# design.net
KiCad netlist of a schematic drawn in Altium Designer
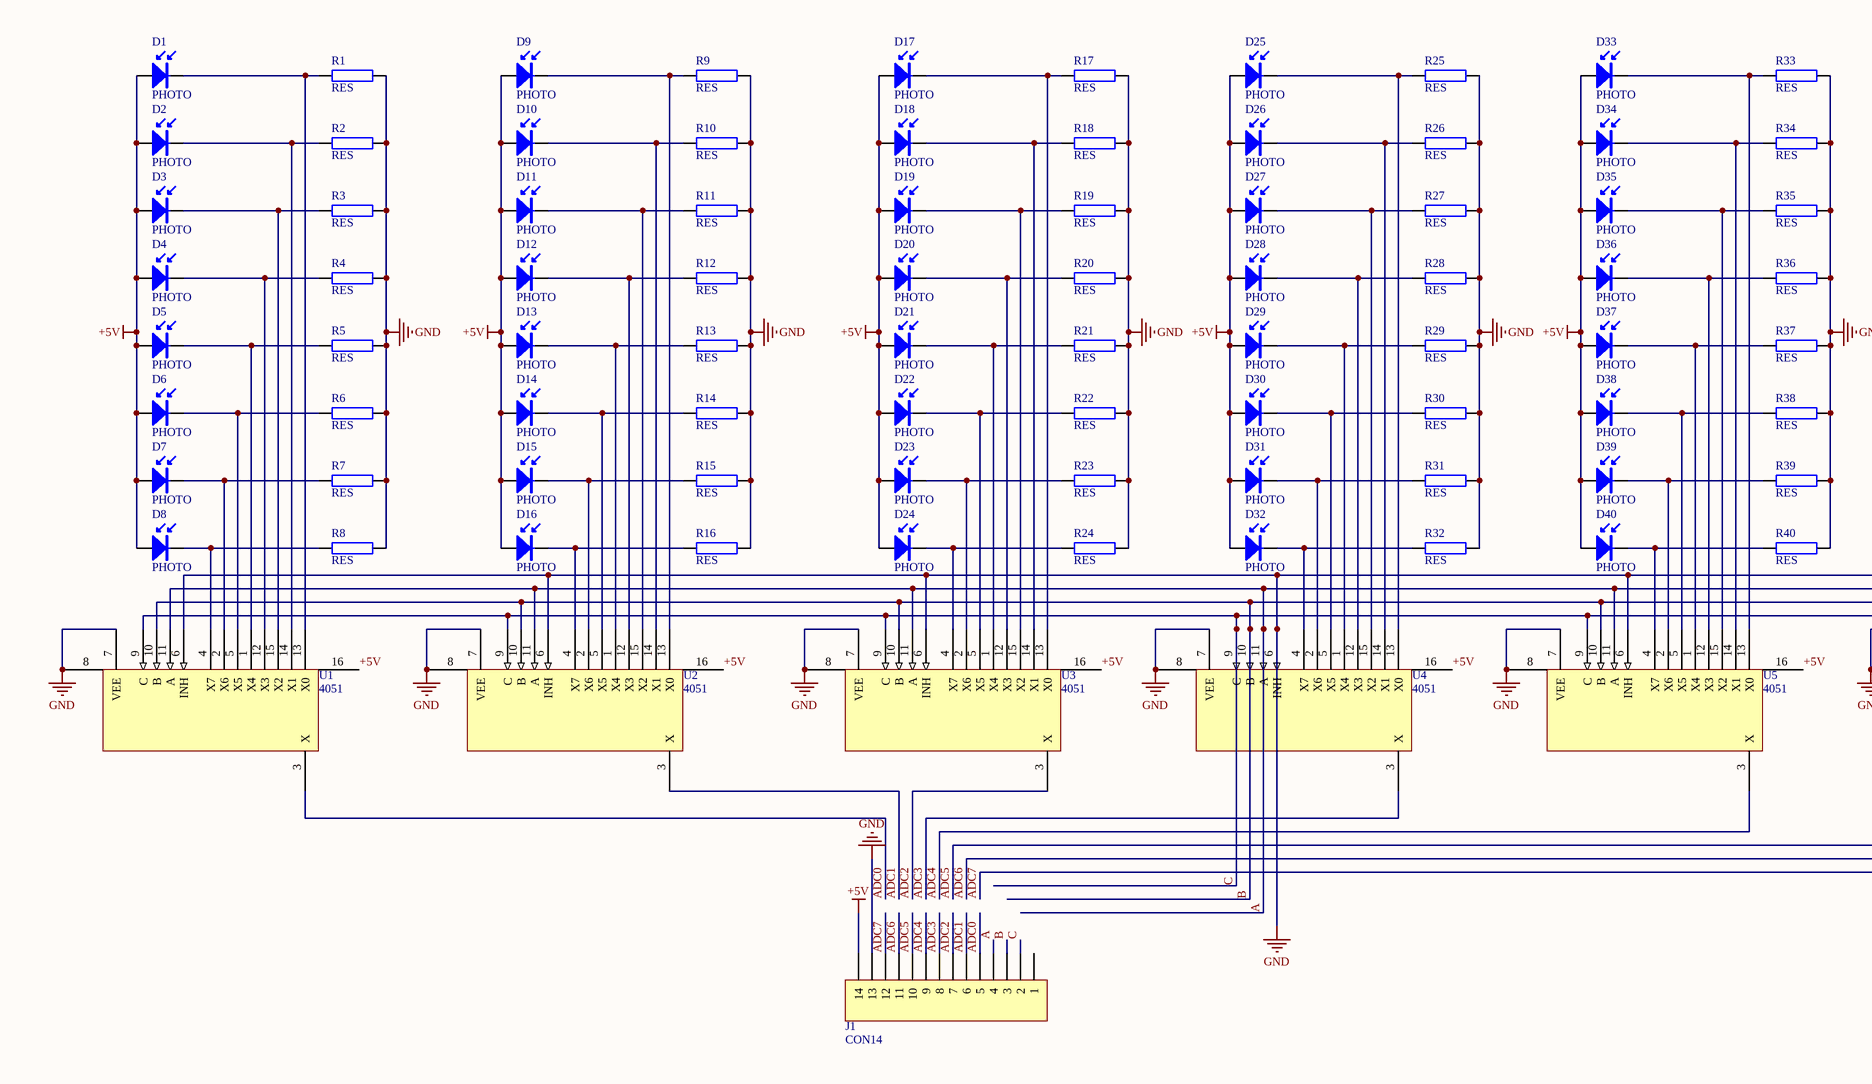
[diagram p0: 光阵列版.SchDoc, left]
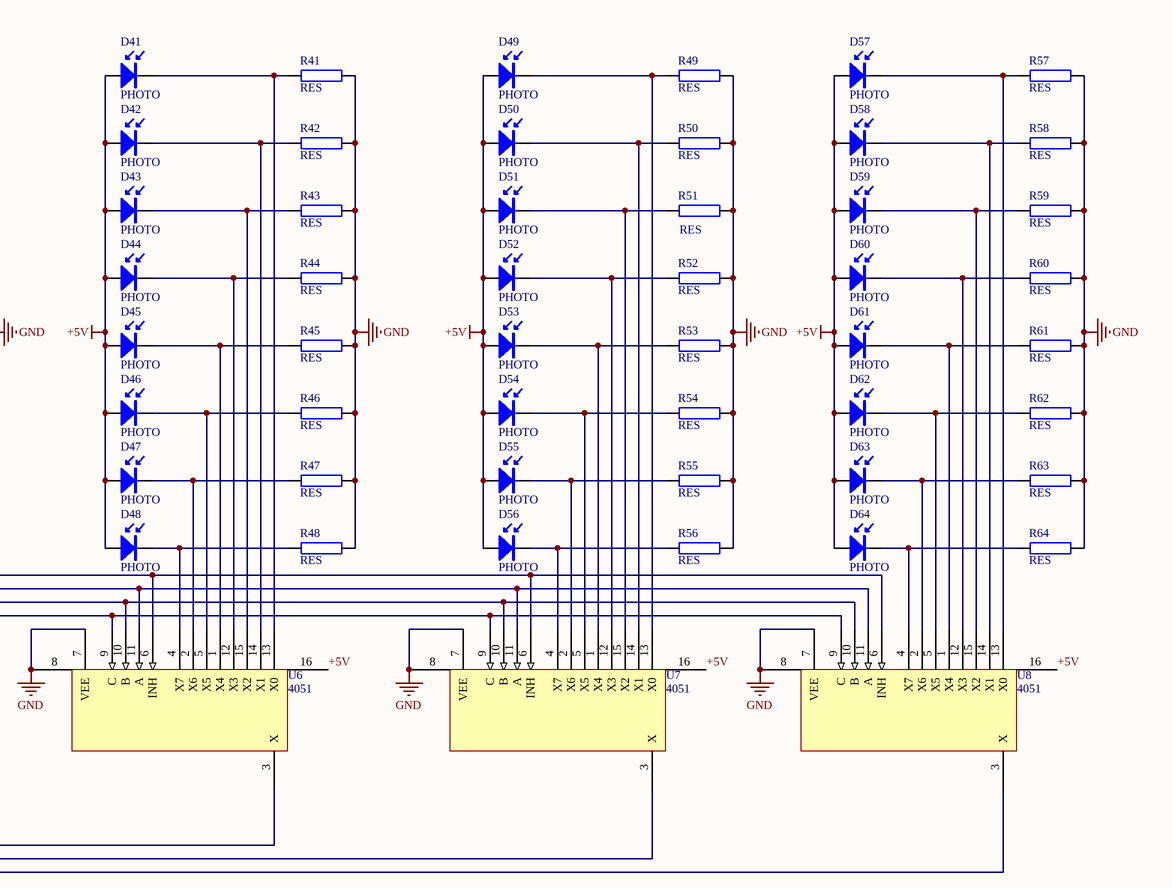
[diagram p1: 光阵列版.SchDoc, right]

(export (version "E")
  (design (tool "Eeschema 10.0.6"))
  (components
    (comp (ref "D1")
      (value "PHOTO")
      (footprint "LED2")
      (description "Photosensitive Diode")
      (libsource (lib "Diode二极管") (part "PHOTO"))
    )
    (comp (ref "D2")
      (value "PHOTO")
      (footprint "LED2")
      (description "Photosensitive Diode")
      (libsource (lib "Diode二极管") (part "PHOTO"))
    )
    (comp (ref "D3")
      (value "PHOTO")
      (footprint "LED2")
      (description "Photosensitive Diode")
      (libsource (lib "Diode二极管") (part "PHOTO"))
    )
    (comp (ref "D4")
      (value "PHOTO")
      (footprint "LED2")
      (description "Photosensitive Diode")
      (libsource (lib "Diode二极管") (part "PHOTO"))
    )
    (comp (ref "D5")
      (value "PHOTO")
      (footprint "LED2")
      (description "Photosensitive Diode")
      (libsource (lib "Diode二极管") (part "PHOTO"))
    )
    (comp (ref "D6")
      (value "PHOTO")
      (footprint "LED2")
      (description "Photosensitive Diode")
      (libsource (lib "Diode二极管") (part "PHOTO"))
    )
    (comp (ref "D7")
      (value "PHOTO")
      (footprint "LED2")
      (description "Photosensitive Diode")
      (libsource (lib "Diode二极管") (part "PHOTO"))
    )
    (comp (ref "D8")
      (value "PHOTO")
      (footprint "LED2")
      (description "Photosensitive Diode")
      (libsource (lib "Diode二极管") (part "PHOTO"))
    )
    (comp (ref "D9")
      (value "PHOTO")
      (footprint "LED2")
      (description "Photosensitive Diode")
      (libsource (lib "Diode二极管") (part "PHOTO"))
    )
    (comp (ref "D10")
      (value "PHOTO")
      (footprint "LED2")
      (description "Photosensitive Diode")
      (libsource (lib "Diode二极管") (part "PHOTO"))
    )
    (comp (ref "D11")
      (value "PHOTO")
      (footprint "LED2")
      (description "Photosensitive Diode")
      (libsource (lib "Diode二极管") (part "PHOTO"))
    )
    (comp (ref "D12")
      (value "PHOTO")
      (footprint "LED2")
      (description "Photosensitive Diode")
      (libsource (lib "Diode二极管") (part "PHOTO"))
    )
    (comp (ref "D13")
      (value "PHOTO")
      (footprint "LED2")
      (description "Photosensitive Diode")
      (libsource (lib "Diode二极管") (part "PHOTO"))
    )
    (comp (ref "D14")
      (value "PHOTO")
      (footprint "LED2")
      (description "Photosensitive Diode")
      (libsource (lib "Diode二极管") (part "PHOTO"))
    )
    (comp (ref "D15")
      (value "PHOTO")
      (footprint "LED2")
      (description "Photosensitive Diode")
      (libsource (lib "Diode二极管") (part "PHOTO"))
    )
    (comp (ref "D16")
      (value "PHOTO")
      (footprint "LED2")
      (description "Photosensitive Diode")
      (libsource (lib "Diode二极管") (part "PHOTO"))
    )
    (comp (ref "D17")
      (value "PHOTO")
      (footprint "LED2")
      (description "Photosensitive Diode")
      (libsource (lib "Diode二极管") (part "PHOTO"))
    )
    (comp (ref "D18")
      (value "PHOTO")
      (footprint "LED2")
      (description "Photosensitive Diode")
      (libsource (lib "Diode二极管") (part "PHOTO"))
    )
    (comp (ref "D19")
      (value "PHOTO")
      (footprint "LED2")
      (description "Photosensitive Diode")
      (libsource (lib "Diode二极管") (part "PHOTO"))
    )
    (comp (ref "D20")
      (value "PHOTO")
      (footprint "LED2")
      (description "Photosensitive Diode")
      (libsource (lib "Diode二极管") (part "PHOTO"))
    )
    (comp (ref "D21")
      (value "PHOTO")
      (footprint "LED2")
      (description "Photosensitive Diode")
      (libsource (lib "Diode二极管") (part "PHOTO"))
    )
    (comp (ref "D22")
      (value "PHOTO")
      (footprint "LED2")
      (description "Photosensitive Diode")
      (libsource (lib "Diode二极管") (part "PHOTO"))
    )
    (comp (ref "D23")
      (value "PHOTO")
      (footprint "LED2")
      (description "Photosensitive Diode")
      (libsource (lib "Diode二极管") (part "PHOTO"))
    )
    (comp (ref "D24")
      (value "PHOTO")
      (footprint "LED2")
      (description "Photosensitive Diode")
      (libsource (lib "Diode二极管") (part "PHOTO"))
    )
    (comp (ref "D25")
      (value "PHOTO")
      (footprint "LED2")
      (description "Photosensitive Diode")
      (libsource (lib "Diode二极管") (part "PHOTO"))
    )
    (comp (ref "D26")
      (value "PHOTO")
      (footprint "LED2")
      (description "Photosensitive Diode")
      (libsource (lib "Diode二极管") (part "PHOTO"))
    )
    (comp (ref "D27")
      (value "PHOTO")
      (footprint "LED2")
      (description "Photosensitive Diode")
      (libsource (lib "Diode二极管") (part "PHOTO"))
    )
    (comp (ref "D28")
      (value "PHOTO")
      (footprint "LED2")
      (description "Photosensitive Diode")
      (libsource (lib "Diode二极管") (part "PHOTO"))
    )
    (comp (ref "D29")
      (value "PHOTO")
      (footprint "LED2")
      (description "Photosensitive Diode")
      (libsource (lib "Diode二极管") (part "PHOTO"))
    )
    (comp (ref "D30")
      (value "PHOTO")
      (footprint "LED2")
      (description "Photosensitive Diode")
      (libsource (lib "Diode二极管") (part "PHOTO"))
    )
    (comp (ref "D31")
      (value "PHOTO")
      (footprint "LED2")
      (description "Photosensitive Diode")
      (libsource (lib "Diode二极管") (part "PHOTO"))
    )
    (comp (ref "D32")
      (value "PHOTO")
      (footprint "LED2")
      (description "Photosensitive Diode")
      (libsource (lib "Diode二极管") (part "PHOTO"))
    )
    (comp (ref "D33")
      (value "PHOTO")
      (footprint "LED2")
      (description "Photosensitive Diode")
      (libsource (lib "Diode二极管") (part "PHOTO"))
    )
    (comp (ref "D34")
      (value "PHOTO")
      (footprint "LED2")
      (description "Photosensitive Diode")
      (libsource (lib "Diode二极管") (part "PHOTO"))
    )
    (comp (ref "D35")
      (value "PHOTO")
      (footprint "LED2")
      (description "Photosensitive Diode")
      (libsource (lib "Diode二极管") (part "PHOTO"))
    )
    (comp (ref "D36")
      (value "PHOTO")
      (footprint "LED2")
      (description "Photosensitive Diode")
      (libsource (lib "Diode二极管") (part "PHOTO"))
    )
    (comp (ref "D37")
      (value "PHOTO")
      (footprint "LED2")
      (description "Photosensitive Diode")
      (libsource (lib "Diode二极管") (part "PHOTO"))
    )
    (comp (ref "D38")
      (value "PHOTO")
      (footprint "LED2")
      (description "Photosensitive Diode")
      (libsource (lib "Diode二极管") (part "PHOTO"))
    )
    (comp (ref "D39")
      (value "PHOTO")
      (footprint "LED2")
      (description "Photosensitive Diode")
      (libsource (lib "Diode二极管") (part "PHOTO"))
    )
    (comp (ref "D40")
      (value "PHOTO")
      (footprint "LED2")
      (description "Photosensitive Diode")
      (libsource (lib "Diode二极管") (part "PHOTO"))
    )
    (comp (ref "D41")
      (value "PHOTO")
      (footprint "LED2")
      (description "Photosensitive Diode")
      (libsource (lib "Diode二极管") (part "PHOTO"))
    )
    (comp (ref "D42")
      (value "PHOTO")
      (footprint "LED2")
      (description "Photosensitive Diode")
      (libsource (lib "Diode二极管") (part "PHOTO"))
    )
    (comp (ref "D43")
      (value "PHOTO")
      (footprint "LED2")
      (description "Photosensitive Diode")
      (libsource (lib "Diode二极管") (part "PHOTO"))
    )
    (comp (ref "D44")
      (value "PHOTO")
      (footprint "LED2")
      (description "Photosensitive Diode")
      (libsource (lib "Diode二极管") (part "PHOTO"))
    )
    (comp (ref "D45")
      (value "PHOTO")
      (footprint "LED2")
      (description "Photosensitive Diode")
      (libsource (lib "Diode二极管") (part "PHOTO"))
    )
    (comp (ref "D46")
      (value "PHOTO")
      (footprint "LED2")
      (description "Photosensitive Diode")
      (libsource (lib "Diode二极管") (part "PHOTO"))
    )
    (comp (ref "D47")
      (value "PHOTO")
      (footprint "LED2")
      (description "Photosensitive Diode")
      (libsource (lib "Diode二极管") (part "PHOTO"))
    )
    (comp (ref "D48")
      (value "PHOTO")
      (footprint "LED2")
      (description "Photosensitive Diode")
      (libsource (lib "Diode二极管") (part "PHOTO"))
    )
    (comp (ref "D49")
      (value "PHOTO")
      (footprint "LED2")
      (description "Photosensitive Diode")
      (libsource (lib "Diode二极管") (part "PHOTO"))
    )
    (comp (ref "D50")
      (value "PHOTO")
      (footprint "LED2")
      (description "Photosensitive Diode")
      (libsource (lib "Diode二极管") (part "PHOTO"))
    )
    (comp (ref "D51")
      (value "PHOTO")
      (footprint "LED2")
      (description "Photosensitive Diode")
      (libsource (lib "Diode二极管") (part "PHOTO"))
    )
    (comp (ref "D52")
      (value "PHOTO")
      (footprint "LED2")
      (description "Photosensitive Diode")
      (libsource (lib "Diode二极管") (part "PHOTO"))
    )
    (comp (ref "D53")
      (value "PHOTO")
      (footprint "LED2")
      (description "Photosensitive Diode")
      (libsource (lib "Diode二极管") (part "PHOTO"))
    )
    (comp (ref "D54")
      (value "PHOTO")
      (footprint "LED2")
      (description "Photosensitive Diode")
      (libsource (lib "Diode二极管") (part "PHOTO"))
    )
    (comp (ref "D55")
      (value "PHOTO")
      (footprint "LED2")
      (description "Photosensitive Diode")
      (libsource (lib "Diode二极管") (part "PHOTO"))
    )
    (comp (ref "D56")
      (value "PHOTO")
      (footprint "LED2")
      (description "Photosensitive Diode")
      (libsource (lib "Diode二极管") (part "PHOTO"))
    )
    (comp (ref "D57")
      (value "PHOTO")
      (footprint "LED2")
      (description "Photosensitive Diode")
      (libsource (lib "Diode二极管") (part "PHOTO"))
    )
    (comp (ref "D58")
      (value "PHOTO")
      (footprint "LED2")
      (description "Photosensitive Diode")
      (libsource (lib "Diode二极管") (part "PHOTO"))
    )
    (comp (ref "D59")
      (value "PHOTO")
      (footprint "LED2")
      (description "Photosensitive Diode")
      (libsource (lib "Diode二极管") (part "PHOTO"))
    )
    (comp (ref "D60")
      (value "PHOTO")
      (footprint "LED2")
      (description "Photosensitive Diode")
      (libsource (lib "Diode二极管") (part "PHOTO"))
    )
    (comp (ref "D61")
      (value "PHOTO")
      (footprint "LED2")
      (description "Photosensitive Diode")
      (libsource (lib "Diode二极管") (part "PHOTO"))
    )
    (comp (ref "D62")
      (value "PHOTO")
      (footprint "LED2")
      (description "Photosensitive Diode")
      (libsource (lib "Diode二极管") (part "PHOTO"))
    )
    (comp (ref "D63")
      (value "PHOTO")
      (footprint "LED2")
      (description "Photosensitive Diode")
      (libsource (lib "Diode二极管") (part "PHOTO"))
    )
    (comp (ref "D64")
      (value "PHOTO")
      (footprint "LED2")
      (description "Photosensitive Diode")
      (libsource (lib "Diode二极管") (part "PHOTO"))
    )
    (comp (ref "J1")
      (value "CON14")
      (footprint "sip-14")
      (description "Connector")
      (libsource (lib "接口") (part "CON14"))
    )
    (comp (ref "R1") (value "RES") (footprint "AXIAL0.3") (libsource (lib "R电阻") (part "RES")))
    (comp (ref "R2") (value "RES") (footprint "AXIAL0.3") (libsource (lib "R电阻") (part "RES")))
    (comp (ref "R3") (value "RES") (footprint "AXIAL0.3") (libsource (lib "R电阻") (part "RES")))
    (comp (ref "R4") (value "RES") (footprint "AXIAL0.3") (libsource (lib "R电阻") (part "RES")))
    (comp (ref "R5") (value "RES") (footprint "AXIAL0.3") (libsource (lib "R电阻") (part "RES")))
    (comp (ref "R6") (value "RES") (footprint "AXIAL0.3") (libsource (lib "R电阻") (part "RES")))
    (comp (ref "R7") (value "RES") (footprint "AXIAL0.3") (libsource (lib "R电阻") (part "RES")))
    (comp (ref "R8") (value "RES") (footprint "AXIAL0.3") (libsource (lib "R电阻") (part "RES")))
    (comp (ref "R9") (value "RES") (footprint "AXIAL0.3") (libsource (lib "R电阻") (part "RES")))
    (comp (ref "R10") (value "RES") (footprint "AXIAL0.3") (libsource (lib "R电阻") (part "RES")))
    (comp (ref "R11") (value "RES") (footprint "AXIAL0.3") (libsource (lib "R电阻") (part "RES")))
    (comp (ref "R12") (value "RES") (footprint "AXIAL0.3") (libsource (lib "R电阻") (part "RES")))
    (comp (ref "R13") (value "RES") (footprint "AXIAL0.3") (libsource (lib "R电阻") (part "RES")))
    (comp (ref "R14") (value "RES") (footprint "AXIAL0.3") (libsource (lib "R电阻") (part "RES")))
    (comp (ref "R15") (value "RES") (footprint "AXIAL0.3") (libsource (lib "R电阻") (part "RES")))
    (comp (ref "R16") (value "RES") (footprint "AXIAL0.3") (libsource (lib "R电阻") (part "RES")))
    (comp (ref "R17") (value "RES") (footprint "AXIAL0.3") (libsource (lib "R电阻") (part "RES")))
    (comp (ref "R18") (value "RES") (footprint "AXIAL0.3") (libsource (lib "R电阻") (part "RES")))
    (comp (ref "R19") (value "RES") (footprint "AXIAL0.3") (libsource (lib "R电阻") (part "RES")))
    (comp (ref "R20") (value "RES") (footprint "AXIAL0.3") (libsource (lib "R电阻") (part "RES")))
    (comp (ref "R21") (value "RES") (footprint "AXIAL0.3") (libsource (lib "R电阻") (part "RES")))
    (comp (ref "R22") (value "RES") (footprint "AXIAL0.3") (libsource (lib "R电阻") (part "RES")))
    (comp (ref "R23") (value "RES") (footprint "AXIAL0.3") (libsource (lib "R电阻") (part "RES")))
    (comp (ref "R24") (value "RES") (footprint "AXIAL0.3") (libsource (lib "R电阻") (part "RES")))
    (comp (ref "R25") (value "RES") (footprint "AXIAL0.3") (libsource (lib "R电阻") (part "RES")))
    (comp (ref "R26") (value "RES") (footprint "AXIAL0.3") (libsource (lib "R电阻") (part "RES")))
    (comp (ref "R27") (value "RES") (footprint "AXIAL0.3") (libsource (lib "R电阻") (part "RES")))
    (comp (ref "R28") (value "RES") (footprint "AXIAL0.3") (libsource (lib "R电阻") (part "RES")))
    (comp (ref "R29") (value "RES") (footprint "AXIAL0.3") (libsource (lib "R电阻") (part "RES")))
    (comp (ref "R30") (value "RES") (footprint "AXIAL0.3") (libsource (lib "R电阻") (part "RES")))
    (comp (ref "R31") (value "RES") (footprint "AXIAL0.3") (libsource (lib "R电阻") (part "RES")))
    (comp (ref "R32") (value "RES") (footprint "AXIAL0.3") (libsource (lib "R电阻") (part "RES")))
    (comp (ref "R33") (value "RES") (footprint "AXIAL0.3") (libsource (lib "R电阻") (part "RES")))
    (comp (ref "R34") (value "RES") (footprint "AXIAL0.3") (libsource (lib "R电阻") (part "RES")))
    (comp (ref "R35") (value "RES") (footprint "AXIAL0.3") (libsource (lib "R电阻") (part "RES")))
    (comp (ref "R36") (value "RES") (footprint "AXIAL0.3") (libsource (lib "R电阻") (part "RES")))
    (comp (ref "R37") (value "RES") (footprint "AXIAL0.3") (libsource (lib "R电阻") (part "RES")))
    (comp (ref "R38") (value "RES") (footprint "AXIAL0.3") (libsource (lib "R电阻") (part "RES")))
    (comp (ref "R39") (value "RES") (footprint "AXIAL0.3") (libsource (lib "R电阻") (part "RES")))
    (comp (ref "R40") (value "RES") (footprint "AXIAL0.3") (libsource (lib "R电阻") (part "RES")))
    (comp (ref "R41") (value "RES") (footprint "AXIAL0.3") (libsource (lib "R电阻") (part "RES")))
    (comp (ref "R42") (value "RES") (footprint "AXIAL0.3") (libsource (lib "R电阻") (part "RES")))
    (comp (ref "R43") (value "RES") (footprint "AXIAL0.3") (libsource (lib "R电阻") (part "RES")))
    (comp (ref "R44") (value "RES") (footprint "AXIAL0.3") (libsource (lib "R电阻") (part "RES")))
    (comp (ref "R45") (value "RES") (footprint "AXIAL0.3") (libsource (lib "R电阻") (part "RES")))
    (comp (ref "R46") (value "RES") (footprint "AXIAL0.3") (libsource (lib "R电阻") (part "RES")))
    (comp (ref "R47") (value "RES") (footprint "AXIAL0.3") (libsource (lib "R电阻") (part "RES")))
    (comp (ref "R48") (value "RES") (footprint "AXIAL0.3") (libsource (lib "R电阻") (part "RES")))
    (comp (ref "R49") (value "RES") (footprint "AXIAL0.3") (libsource (lib "R电阻") (part "RES")))
    (comp (ref "R50") (value "RES") (footprint "AXIAL0.3") (libsource (lib "R电阻") (part "RES")))
    (comp (ref "R51") (value "RES") (footprint "AXIAL0.3") (libsource (lib "R电阻") (part "RES")))
    (comp (ref "R52") (value "RES") (footprint "AXIAL0.3") (libsource (lib "R电阻") (part "RES")))
    (comp (ref "R53") (value "RES") (footprint "AXIAL0.3") (libsource (lib "R电阻") (part "RES")))
    (comp (ref "R54") (value "RES") (footprint "AXIAL0.3") (libsource (lib "R电阻") (part "RES")))
    (comp (ref "R55") (value "RES") (footprint "AXIAL0.3") (libsource (lib "R电阻") (part "RES")))
    (comp (ref "R56") (value "RES") (footprint "AXIAL0.3") (libsource (lib "R电阻") (part "RES")))
    (comp (ref "R57") (value "RES") (footprint "AXIAL0.3") (libsource (lib "R电阻") (part "RES")))
    (comp (ref "R58") (value "RES") (footprint "AXIAL0.3") (libsource (lib "R电阻") (part "RES")))
    (comp (ref "R59") (value "RES") (footprint "AXIAL0.3") (libsource (lib "R电阻") (part "RES")))
    (comp (ref "R60") (value "RES") (footprint "AXIAL0.3") (libsource (lib "R电阻") (part "RES")))
    (comp (ref "R61") (value "RES") (footprint "AXIAL0.3") (libsource (lib "R电阻") (part "RES")))
    (comp (ref "R62") (value "RES") (footprint "AXIAL0.3") (libsource (lib "R电阻") (part "RES")))
    (comp (ref "R63") (value "RES") (footprint "AXIAL0.3") (libsource (lib "R电阻") (part "RES")))
    (comp (ref "R64") (value "RES") (footprint "AXIAL0.3") (libsource (lib "R电阻") (part "RES")))
    (comp (ref "U1") (value "4051") (footprint "SO-16") (libsource (lib "4000 CMOS") (part "4051")))
    (comp (ref "U2") (value "4051") (footprint "SO-16") (libsource (lib "4000 CMOS") (part "4051")))
    (comp (ref "U3") (value "4051") (footprint "SO-16") (libsource (lib "4000 CMOS") (part "4051")))
    (comp (ref "U4") (value "4051") (footprint "SO-16") (libsource (lib "4000 CMOS") (part "4051")))
    (comp (ref "U5") (value "4051") (footprint "SO-16") (libsource (lib "4000 CMOS") (part "4051")))
    (comp (ref "U6") (value "4051") (footprint "SO-16") (libsource (lib "4000 CMOS") (part "4051")))
    (comp (ref "U7") (value "4051") (footprint "SO-16") (libsource (lib "4000 CMOS") (part "4051")))
    (comp (ref "U8") (value "4051") (footprint "SO-16") (libsource (lib "4000 CMOS") (part "4051")))
  )
  (nets
    (net (code "1") (name "+5V") (class "Default")
      (node (ref "D1") (pin "1") (pinfunction "1_1") (pintype "passive"))
      (node (ref "D10") (pin "1") (pinfunction "1_1") (pintype "passive"))
      (node (ref "D11") (pin "1") (pinfunction "1_1") (pintype "passive"))
      (node (ref "D12") (pin "1") (pinfunction "1_1") (pintype "passive"))
      (node (ref "D13") (pin "1") (pinfunction "1_1") (pintype "passive"))
      (node (ref "D14") (pin "1") (pinfunction "1_1") (pintype "passive"))
      (node (ref "D15") (pin "1") (pinfunction "1_1") (pintype "passive"))
      (node (ref "D16") (pin "1") (pinfunction "1_1") (pintype "passive"))
      (node (ref "D17") (pin "1") (pinfunction "1_1") (pintype "passive"))
      (node (ref "D18") (pin "1") (pinfunction "1_1") (pintype "passive"))
      (node (ref "D19") (pin "1") (pinfunction "1_1") (pintype "passive"))
      (node (ref "D2") (pin "1") (pinfunction "1_1") (pintype "passive"))
      (node (ref "D20") (pin "1") (pinfunction "1_1") (pintype "passive"))
      (node (ref "D21") (pin "1") (pinfunction "1_1") (pintype "passive"))
      (node (ref "D22") (pin "1") (pinfunction "1_1") (pintype "passive"))
      (node (ref "D23") (pin "1") (pinfunction "1_1") (pintype "passive"))
      (node (ref "D24") (pin "1") (pinfunction "1_1") (pintype "passive"))
      (node (ref "D25") (pin "1") (pinfunction "1_1") (pintype "passive"))
      (node (ref "D26") (pin "1") (pinfunction "1_1") (pintype "passive"))
      (node (ref "D27") (pin "1") (pinfunction "1_1") (pintype "passive"))
      (node (ref "D28") (pin "1") (pinfunction "1_1") (pintype "passive"))
      (node (ref "D29") (pin "1") (pinfunction "1_1") (pintype "passive"))
      (node (ref "D3") (pin "1") (pinfunction "1_1") (pintype "passive"))
      (node (ref "D30") (pin "1") (pinfunction "1_1") (pintype "passive"))
      (node (ref "D31") (pin "1") (pinfunction "1_1") (pintype "passive"))
      (node (ref "D32") (pin "1") (pinfunction "1_1") (pintype "passive"))
      (node (ref "D33") (pin "1") (pinfunction "1_1") (pintype "passive"))
      (node (ref "D34") (pin "1") (pinfunction "1_1") (pintype "passive"))
      (node (ref "D35") (pin "1") (pinfunction "1_1") (pintype "passive"))
      (node (ref "D36") (pin "1") (pinfunction "1_1") (pintype "passive"))
      (node (ref "D37") (pin "1") (pinfunction "1_1") (pintype "passive"))
      (node (ref "D38") (pin "1") (pinfunction "1_1") (pintype "passive"))
      (node (ref "D39") (pin "1") (pinfunction "1_1") (pintype "passive"))
      (node (ref "D4") (pin "1") (pinfunction "1_1") (pintype "passive"))
      (node (ref "D40") (pin "1") (pinfunction "1_1") (pintype "passive"))
      (node (ref "D41") (pin "1") (pinfunction "1_1") (pintype "passive"))
      (node (ref "D42") (pin "1") (pinfunction "1_1") (pintype "passive"))
      (node (ref "D43") (pin "1") (pinfunction "1_1") (pintype "passive"))
      (node (ref "D44") (pin "1") (pinfunction "1_1") (pintype "passive"))
      (node (ref "D45") (pin "1") (pinfunction "1_1") (pintype "passive"))
      (node (ref "D46") (pin "1") (pinfunction "1_1") (pintype "passive"))
      (node (ref "D47") (pin "1") (pinfunction "1_1") (pintype "passive"))
      (node (ref "D48") (pin "1") (pinfunction "1_1") (pintype "passive"))
      (node (ref "D49") (pin "1") (pinfunction "1_1") (pintype "passive"))
      (node (ref "D5") (pin "1") (pinfunction "1_1") (pintype "passive"))
      (node (ref "D50") (pin "1") (pinfunction "1_1") (pintype "passive"))
      (node (ref "D51") (pin "1") (pinfunction "1_1") (pintype "passive"))
      (node (ref "D52") (pin "1") (pinfunction "1_1") (pintype "passive"))
      (node (ref "D53") (pin "1") (pinfunction "1_1") (pintype "passive"))
      (node (ref "D54") (pin "1") (pinfunction "1_1") (pintype "passive"))
      (node (ref "D55") (pin "1") (pinfunction "1_1") (pintype "passive"))
      (node (ref "D56") (pin "1") (pinfunction "1_1") (pintype "passive"))
      (node (ref "D57") (pin "1") (pinfunction "1_1") (pintype "passive"))
      (node (ref "D58") (pin "1") (pinfunction "1_1") (pintype "passive"))
      (node (ref "D59") (pin "1") (pinfunction "1_1") (pintype "passive"))
      (node (ref "D6") (pin "1") (pinfunction "1_1") (pintype "passive"))
      (node (ref "D60") (pin "1") (pinfunction "1_1") (pintype "passive"))
      (node (ref "D61") (pin "1") (pinfunction "1_1") (pintype "passive"))
      (node (ref "D62") (pin "1") (pinfunction "1_1") (pintype "passive"))
      (node (ref "D63") (pin "1") (pinfunction "1_1") (pintype "passive"))
      (node (ref "D64") (pin "1") (pinfunction "1_1") (pintype "passive"))
      (node (ref "D7") (pin "1") (pinfunction "1_1") (pintype "passive"))
      (node (ref "D8") (pin "1") (pinfunction "1_1") (pintype "passive"))
      (node (ref "D9") (pin "1") (pinfunction "1_1") (pintype "passive"))
      (node (ref "J1") (pin "14") (pinfunction "14_14") (pintype "passive"))
      (node (ref "U1") (pin "16") (pinfunction "VCC_16") (pintype "power_in"))
      (node (ref "U2") (pin "16") (pinfunction "VCC_16") (pintype "power_in"))
      (node (ref "U3") (pin "16") (pinfunction "VCC_16") (pintype "power_in"))
      (node (ref "U4") (pin "16") (pinfunction "VCC_16") (pintype "power_in"))
      (node (ref "U5") (pin "16") (pinfunction "VCC_16") (pintype "power_in"))
      (node (ref "U6") (pin "16") (pinfunction "VCC_16") (pintype "power_in"))
      (node (ref "U7") (pin "16") (pinfunction "VCC_16") (pintype "power_in"))
      (node (ref "U8") (pin "16") (pinfunction "VCC_16") (pintype "power_in"))
    )
    (net (code "2") (name "/A") (class "Default")
      (node (ref "J1") (pin "4") (pinfunction "4_4") (pintype "passive"))
      (node (ref "U1") (pin "11") (pinfunction "A_11") (pintype "input"))
      (node (ref "U2") (pin "11") (pinfunction "A_11") (pintype "input"))
      (node (ref "U3") (pin "11") (pinfunction "A_11") (pintype "input"))
      (node (ref "U4") (pin "11") (pinfunction "A_11") (pintype "input"))
      (node (ref "U5") (pin "11") (pinfunction "A_11") (pintype "input"))
      (node (ref "U6") (pin "11") (pinfunction "A_11") (pintype "input"))
      (node (ref "U7") (pin "11") (pinfunction "A_11") (pintype "input"))
      (node (ref "U8") (pin "11") (pinfunction "A_11") (pintype "input"))
    )
    (net (code "3") (name "/ADC0") (class "Default")
      (node (ref "J1") (pin "5") (pinfunction "5_5") (pintype "passive"))
      (node (ref "U1") (pin "3") (pinfunction "X_3") (pintype "passive"))
    )
    (net (code "4") (name "/ADC1") (class "Default")
      (node (ref "J1") (pin "6") (pinfunction "6_6") (pintype "passive"))
      (node (ref "U2") (pin "3") (pinfunction "X_3") (pintype "passive"))
    )
    (net (code "5") (name "/ADC2") (class "Default")
      (node (ref "J1") (pin "7") (pinfunction "7_7") (pintype "passive"))
      (node (ref "U3") (pin "3") (pinfunction "X_3") (pintype "passive"))
    )
    (net (code "6") (name "/ADC3") (class "Default")
      (node (ref "J1") (pin "8") (pinfunction "8_8") (pintype "passive"))
      (node (ref "U4") (pin "3") (pinfunction "X_3") (pintype "passive"))
    )
    (net (code "7") (name "/ADC4") (class "Default")
      (node (ref "J1") (pin "9") (pinfunction "9_9") (pintype "passive"))
      (node (ref "U5") (pin "3") (pinfunction "X_3") (pintype "passive"))
    )
    (net (code "8") (name "/ADC5") (class "Default")
      (node (ref "J1") (pin "10") (pinfunction "10_10") (pintype "passive"))
      (node (ref "U6") (pin "3") (pinfunction "X_3") (pintype "passive"))
    )
    (net (code "9") (name "/ADC6") (class "Default")
      (node (ref "J1") (pin "11") (pinfunction "11_11") (pintype "passive"))
      (node (ref "U7") (pin "3") (pinfunction "X_3") (pintype "passive"))
    )
    (net (code "10") (name "/ADC7") (class "Default")
      (node (ref "J1") (pin "12") (pinfunction "12_12") (pintype "passive"))
      (node (ref "U8") (pin "3") (pinfunction "X_3") (pintype "passive"))
    )
    (net (code "11") (name "/B") (class "Default")
      (node (ref "J1") (pin "3") (pinfunction "3_3") (pintype "passive"))
      (node (ref "U1") (pin "10") (pinfunction "B_10") (pintype "input"))
      (node (ref "U2") (pin "10") (pinfunction "B_10") (pintype "input"))
      (node (ref "U3") (pin "10") (pinfunction "B_10") (pintype "input"))
      (node (ref "U4") (pin "10") (pinfunction "B_10") (pintype "input"))
      (node (ref "U5") (pin "10") (pinfunction "B_10") (pintype "input"))
      (node (ref "U6") (pin "10") (pinfunction "B_10") (pintype "input"))
      (node (ref "U7") (pin "10") (pinfunction "B_10") (pintype "input"))
      (node (ref "U8") (pin "10") (pinfunction "B_10") (pintype "input"))
    )
    (net (code "12") (name "/C") (class "Default")
      (node (ref "J1") (pin "2") (pinfunction "2_2") (pintype "passive"))
      (node (ref "U1") (pin "9") (pinfunction "C_9") (pintype "input"))
      (node (ref "U2") (pin "9") (pinfunction "C_9") (pintype "input"))
      (node (ref "U3") (pin "9") (pinfunction "C_9") (pintype "input"))
      (node (ref "U4") (pin "9") (pinfunction "C_9") (pintype "input"))
      (node (ref "U5") (pin "9") (pinfunction "C_9") (pintype "input"))
      (node (ref "U6") (pin "9") (pinfunction "C_9") (pintype "input"))
      (node (ref "U7") (pin "9") (pinfunction "C_9") (pintype "input"))
      (node (ref "U8") (pin "9") (pinfunction "C_9") (pintype "input"))
    )
    (net (code "13") (name "GND") (class "Default")
      (node (ref "J1") (pin "13") (pinfunction "13_13") (pintype "passive"))
      (node (ref "R1") (pin "2") (pinfunction "2_2") (pintype "passive"))
      (node (ref "R10") (pin "2") (pinfunction "2_2") (pintype "passive"))
      (node (ref "R11") (pin "2") (pinfunction "2_2") (pintype "passive"))
      (node (ref "R12") (pin "2") (pinfunction "2_2") (pintype "passive"))
      (node (ref "R13") (pin "2") (pinfunction "2_2") (pintype "passive"))
      (node (ref "R14") (pin "2") (pinfunction "2_2") (pintype "passive"))
      (node (ref "R15") (pin "2") (pinfunction "2_2") (pintype "passive"))
      (node (ref "R16") (pin "2") (pinfunction "2_2") (pintype "passive"))
      (node (ref "R17") (pin "2") (pinfunction "2_2") (pintype "passive"))
      (node (ref "R18") (pin "2") (pinfunction "2_2") (pintype "passive"))
      (node (ref "R19") (pin "2") (pinfunction "2_2") (pintype "passive"))
      (node (ref "R2") (pin "2") (pinfunction "2_2") (pintype "passive"))
      (node (ref "R20") (pin "2") (pinfunction "2_2") (pintype "passive"))
      (node (ref "R21") (pin "2") (pinfunction "2_2") (pintype "passive"))
      (node (ref "R22") (pin "2") (pinfunction "2_2") (pintype "passive"))
      (node (ref "R23") (pin "2") (pinfunction "2_2") (pintype "passive"))
      (node (ref "R24") (pin "2") (pinfunction "2_2") (pintype "passive"))
      (node (ref "R25") (pin "2") (pinfunction "2_2") (pintype "passive"))
      (node (ref "R26") (pin "2") (pinfunction "2_2") (pintype "passive"))
      (node (ref "R27") (pin "2") (pinfunction "2_2") (pintype "passive"))
      (node (ref "R28") (pin "2") (pinfunction "2_2") (pintype "passive"))
      (node (ref "R29") (pin "2") (pinfunction "2_2") (pintype "passive"))
      (node (ref "R3") (pin "2") (pinfunction "2_2") (pintype "passive"))
      (node (ref "R30") (pin "2") (pinfunction "2_2") (pintype "passive"))
      (node (ref "R31") (pin "2") (pinfunction "2_2") (pintype "passive"))
      (node (ref "R32") (pin "2") (pinfunction "2_2") (pintype "passive"))
      (node (ref "R33") (pin "2") (pinfunction "2_2") (pintype "passive"))
      (node (ref "R34") (pin "2") (pinfunction "2_2") (pintype "passive"))
      (node (ref "R35") (pin "2") (pinfunction "2_2") (pintype "passive"))
      (node (ref "R36") (pin "2") (pinfunction "2_2") (pintype "passive"))
      (node (ref "R37") (pin "2") (pinfunction "2_2") (pintype "passive"))
      (node (ref "R38") (pin "2") (pinfunction "2_2") (pintype "passive"))
      (node (ref "R39") (pin "2") (pinfunction "2_2") (pintype "passive"))
      (node (ref "R4") (pin "2") (pinfunction "2_2") (pintype "passive"))
      (node (ref "R40") (pin "2") (pinfunction "2_2") (pintype "passive"))
      (node (ref "R41") (pin "2") (pinfunction "2_2") (pintype "passive"))
      (node (ref "R42") (pin "2") (pinfunction "2_2") (pintype "passive"))
      (node (ref "R43") (pin "2") (pinfunction "2_2") (pintype "passive"))
      (node (ref "R44") (pin "2") (pinfunction "2_2") (pintype "passive"))
      (node (ref "R45") (pin "2") (pinfunction "2_2") (pintype "passive"))
      (node (ref "R46") (pin "2") (pinfunction "2_2") (pintype "passive"))
      (node (ref "R47") (pin "2") (pinfunction "2_2") (pintype "passive"))
      (node (ref "R48") (pin "2") (pinfunction "2_2") (pintype "passive"))
      (node (ref "R49") (pin "2") (pinfunction "2_2") (pintype "passive"))
      (node (ref "R5") (pin "2") (pinfunction "2_2") (pintype "passive"))
      (node (ref "R50") (pin "2") (pinfunction "2_2") (pintype "passive"))
      (node (ref "R51") (pin "2") (pinfunction "2_2") (pintype "passive"))
      (node (ref "R52") (pin "2") (pinfunction "2_2") (pintype "passive"))
      (node (ref "R53") (pin "2") (pinfunction "2_2") (pintype "passive"))
      (node (ref "R54") (pin "2") (pinfunction "2_2") (pintype "passive"))
      (node (ref "R55") (pin "2") (pinfunction "2_2") (pintype "passive"))
      (node (ref "R56") (pin "2") (pinfunction "2_2") (pintype "passive"))
      (node (ref "R57") (pin "2") (pinfunction "2_2") (pintype "passive"))
      (node (ref "R58") (pin "2") (pinfunction "2_2") (pintype "passive"))
      (node (ref "R59") (pin "2") (pinfunction "2_2") (pintype "passive"))
      (node (ref "R6") (pin "2") (pinfunction "2_2") (pintype "passive"))
      (node (ref "R60") (pin "2") (pinfunction "2_2") (pintype "passive"))
      (node (ref "R61") (pin "2") (pinfunction "2_2") (pintype "passive"))
      (node (ref "R62") (pin "2") (pinfunction "2_2") (pintype "passive"))
      (node (ref "R63") (pin "2") (pinfunction "2_2") (pintype "passive"))
      (node (ref "R64") (pin "2") (pinfunction "2_2") (pintype "passive"))
      (node (ref "R7") (pin "2") (pinfunction "2_2") (pintype "passive"))
      (node (ref "R8") (pin "2") (pinfunction "2_2") (pintype "passive"))
      (node (ref "R9") (pin "2") (pinfunction "2_2") (pintype "passive"))
      (node (ref "U1") (pin "6") (pinfunction "INH_6") (pintype "input"))
      (node (ref "U1") (pin "7") (pinfunction "VEE_7") (pintype "passive"))
      (node (ref "U1") (pin "8") (pinfunction "GND_8") (pintype "power_in"))
      (node (ref "U2") (pin "6") (pinfunction "INH_6") (pintype "input"))
      (node (ref "U2") (pin "7") (pinfunction "VEE_7") (pintype "passive"))
      (node (ref "U2") (pin "8") (pinfunction "GND_8") (pintype "power_in"))
      (node (ref "U3") (pin "6") (pinfunction "INH_6") (pintype "input"))
      (node (ref "U3") (pin "7") (pinfunction "VEE_7") (pintype "passive"))
      (node (ref "U3") (pin "8") (pinfunction "GND_8") (pintype "power_in"))
      (node (ref "U4") (pin "6") (pinfunction "INH_6") (pintype "input"))
      (node (ref "U4") (pin "7") (pinfunction "VEE_7") (pintype "passive"))
      (node (ref "U4") (pin "8") (pinfunction "GND_8") (pintype "power_in"))
      (node (ref "U5") (pin "6") (pinfunction "INH_6") (pintype "input"))
      (node (ref "U5") (pin "7") (pinfunction "VEE_7") (pintype "passive"))
      (node (ref "U5") (pin "8") (pinfunction "GND_8") (pintype "power_in"))
      (node (ref "U6") (pin "6") (pinfunction "INH_6") (pintype "input"))
      (node (ref "U6") (pin "7") (pinfunction "VEE_7") (pintype "passive"))
      (node (ref "U6") (pin "8") (pinfunction "GND_8") (pintype "power_in"))
      (node (ref "U7") (pin "6") (pinfunction "INH_6") (pintype "input"))
      (node (ref "U7") (pin "7") (pinfunction "VEE_7") (pintype "passive"))
      (node (ref "U7") (pin "8") (pinfunction "GND_8") (pintype "power_in"))
      (node (ref "U8") (pin "6") (pinfunction "INH_6") (pintype "input"))
      (node (ref "U8") (pin "7") (pinfunction "VEE_7") (pintype "passive"))
      (node (ref "U8") (pin "8") (pinfunction "GND_8") (pintype "power_in"))
    )
    (net (code "14") (name "Net-(U1-X0)") (class "Default")
      (node (ref "D1") (pin "2") (pinfunction "2_2") (pintype "passive"))
      (node (ref "R1") (pin "1") (pinfunction "1_1") (pintype "passive"))
      (node (ref "U1") (pin "13") (pinfunction "X0_13") (pintype "passive"))
    )
    (net (code "15") (name "Net-(U1-X1)") (class "Default")
      (node (ref "D2") (pin "2") (pinfunction "2_2") (pintype "passive"))
      (node (ref "R2") (pin "1") (pinfunction "1_1") (pintype "passive"))
      (node (ref "U1") (pin "14") (pinfunction "X1_14") (pintype "passive"))
    )
    (net (code "16") (name "Net-(U1-X2)") (class "Default")
      (node (ref "D3") (pin "2") (pinfunction "2_2") (pintype "passive"))
      (node (ref "R3") (pin "1") (pinfunction "1_1") (pintype "passive"))
      (node (ref "U1") (pin "15") (pinfunction "X2_15") (pintype "passive"))
    )
    (net (code "17") (name "Net-(U1-X3)") (class "Default")
      (node (ref "D4") (pin "2") (pinfunction "2_2") (pintype "passive"))
      (node (ref "R4") (pin "1") (pinfunction "1_1") (pintype "passive"))
      (node (ref "U1") (pin "12") (pinfunction "X3_12") (pintype "passive"))
    )
    (net (code "18") (name "Net-(U1-X4)") (class "Default")
      (node (ref "D5") (pin "2") (pinfunction "2_2") (pintype "passive"))
      (node (ref "R5") (pin "1") (pinfunction "1_1") (pintype "passive"))
      (node (ref "U1") (pin "1") (pinfunction "X4_1") (pintype "passive"))
    )
    (net (code "19") (name "Net-(U1-X5)") (class "Default")
      (node (ref "D6") (pin "2") (pinfunction "2_2") (pintype "passive"))
      (node (ref "R6") (pin "1") (pinfunction "1_1") (pintype "passive"))
      (node (ref "U1") (pin "5") (pinfunction "X5_5") (pintype "passive"))
    )
    (net (code "20") (name "Net-(U1-X6)") (class "Default")
      (node (ref "D7") (pin "2") (pinfunction "2_2") (pintype "passive"))
      (node (ref "R7") (pin "1") (pinfunction "1_1") (pintype "passive"))
      (node (ref "U1") (pin "2") (pinfunction "X6_2") (pintype "passive"))
    )
    (net (code "21") (name "Net-(U1-X7)") (class "Default")
      (node (ref "D8") (pin "2") (pinfunction "2_2") (pintype "passive"))
      (node (ref "R8") (pin "1") (pinfunction "1_1") (pintype "passive"))
      (node (ref "U1") (pin "4") (pinfunction "X7_4") (pintype "passive"))
    )
    (net (code "22") (name "Net-(U2-X0)") (class "Default")
      (node (ref "D9") (pin "2") (pinfunction "2_2") (pintype "passive"))
      (node (ref "R9") (pin "1") (pinfunction "1_1") (pintype "passive"))
      (node (ref "U2") (pin "13") (pinfunction "X0_13") (pintype "passive"))
    )
    (net (code "23") (name "Net-(U2-X1)") (class "Default")
      (node (ref "D10") (pin "2") (pinfunction "2_2") (pintype "passive"))
      (node (ref "R10") (pin "1") (pinfunction "1_1") (pintype "passive"))
      (node (ref "U2") (pin "14") (pinfunction "X1_14") (pintype "passive"))
    )
    (net (code "24") (name "Net-(U2-X2)") (class "Default")
      (node (ref "D11") (pin "2") (pinfunction "2_2") (pintype "passive"))
      (node (ref "R11") (pin "1") (pinfunction "1_1") (pintype "passive"))
      (node (ref "U2") (pin "15") (pinfunction "X2_15") (pintype "passive"))
    )
    (net (code "25") (name "Net-(U2-X3)") (class "Default")
      (node (ref "D12") (pin "2") (pinfunction "2_2") (pintype "passive"))
      (node (ref "R12") (pin "1") (pinfunction "1_1") (pintype "passive"))
      (node (ref "U2") (pin "12") (pinfunction "X3_12") (pintype "passive"))
    )
    (net (code "26") (name "Net-(U2-X4)") (class "Default")
      (node (ref "D13") (pin "2") (pinfunction "2_2") (pintype "passive"))
      (node (ref "R13") (pin "1") (pinfunction "1_1") (pintype "passive"))
      (node (ref "U2") (pin "1") (pinfunction "X4_1") (pintype "passive"))
    )
    (net (code "27") (name "Net-(U2-X5)") (class "Default")
      (node (ref "D14") (pin "2") (pinfunction "2_2") (pintype "passive"))
      (node (ref "R14") (pin "1") (pinfunction "1_1") (pintype "passive"))
      (node (ref "U2") (pin "5") (pinfunction "X5_5") (pintype "passive"))
    )
    (net (code "28") (name "Net-(U2-X6)") (class "Default")
      (node (ref "D15") (pin "2") (pinfunction "2_2") (pintype "passive"))
      (node (ref "R15") (pin "1") (pinfunction "1_1") (pintype "passive"))
      (node (ref "U2") (pin "2") (pinfunction "X6_2") (pintype "passive"))
    )
    (net (code "29") (name "Net-(U2-X7)") (class "Default")
      (node (ref "D16") (pin "2") (pinfunction "2_2") (pintype "passive"))
      (node (ref "R16") (pin "1") (pinfunction "1_1") (pintype "passive"))
      (node (ref "U2") (pin "4") (pinfunction "X7_4") (pintype "passive"))
    )
    (net (code "30") (name "Net-(U3-X0)") (class "Default")
      (node (ref "D17") (pin "2") (pinfunction "2_2") (pintype "passive"))
      (node (ref "R17") (pin "1") (pinfunction "1_1") (pintype "passive"))
      (node (ref "U3") (pin "13") (pinfunction "X0_13") (pintype "passive"))
    )
    (net (code "31") (name "Net-(U3-X1)") (class "Default")
      (node (ref "D18") (pin "2") (pinfunction "2_2") (pintype "passive"))
      (node (ref "R18") (pin "1") (pinfunction "1_1") (pintype "passive"))
      (node (ref "U3") (pin "14") (pinfunction "X1_14") (pintype "passive"))
    )
    (net (code "32") (name "Net-(U3-X2)") (class "Default")
      (node (ref "D19") (pin "2") (pinfunction "2_2") (pintype "passive"))
      (node (ref "R19") (pin "1") (pinfunction "1_1") (pintype "passive"))
      (node (ref "U3") (pin "15") (pinfunction "X2_15") (pintype "passive"))
    )
    (net (code "33") (name "Net-(U3-X3)") (class "Default")
      (node (ref "D20") (pin "2") (pinfunction "2_2") (pintype "passive"))
      (node (ref "R20") (pin "1") (pinfunction "1_1") (pintype "passive"))
      (node (ref "U3") (pin "12") (pinfunction "X3_12") (pintype "passive"))
    )
    (net (code "34") (name "Net-(U3-X4)") (class "Default")
      (node (ref "D21") (pin "2") (pinfunction "2_2") (pintype "passive"))
      (node (ref "R21") (pin "1") (pinfunction "1_1") (pintype "passive"))
      (node (ref "U3") (pin "1") (pinfunction "X4_1") (pintype "passive"))
    )
    (net (code "35") (name "Net-(U3-X5)") (class "Default")
      (node (ref "D22") (pin "2") (pinfunction "2_2") (pintype "passive"))
      (node (ref "R22") (pin "1") (pinfunction "1_1") (pintype "passive"))
      (node (ref "U3") (pin "5") (pinfunction "X5_5") (pintype "passive"))
    )
    (net (code "36") (name "Net-(U3-X6)") (class "Default")
      (node (ref "D23") (pin "2") (pinfunction "2_2") (pintype "passive"))
      (node (ref "R23") (pin "1") (pinfunction "1_1") (pintype "passive"))
      (node (ref "U3") (pin "2") (pinfunction "X6_2") (pintype "passive"))
    )
    (net (code "37") (name "Net-(U3-X7)") (class "Default")
      (node (ref "D24") (pin "2") (pinfunction "2_2") (pintype "passive"))
      (node (ref "R24") (pin "1") (pinfunction "1_1") (pintype "passive"))
      (node (ref "U3") (pin "4") (pinfunction "X7_4") (pintype "passive"))
    )
    (net (code "38") (name "Net-(U4-X0)") (class "Default")
      (node (ref "D25") (pin "2") (pinfunction "2_2") (pintype "passive"))
      (node (ref "R25") (pin "1") (pinfunction "1_1") (pintype "passive"))
      (node (ref "U4") (pin "13") (pinfunction "X0_13") (pintype "passive"))
    )
    (net (code "39") (name "Net-(U4-X1)") (class "Default")
      (node (ref "D26") (pin "2") (pinfunction "2_2") (pintype "passive"))
      (node (ref "R26") (pin "1") (pinfunction "1_1") (pintype "passive"))
      (node (ref "U4") (pin "14") (pinfunction "X1_14") (pintype "passive"))
    )
    (net (code "40") (name "Net-(U4-X2)") (class "Default")
      (node (ref "D27") (pin "2") (pinfunction "2_2") (pintype "passive"))
      (node (ref "R27") (pin "1") (pinfunction "1_1") (pintype "passive"))
      (node (ref "U4") (pin "15") (pinfunction "X2_15") (pintype "passive"))
    )
    (net (code "41") (name "Net-(U4-X3)") (class "Default")
      (node (ref "D28") (pin "2") (pinfunction "2_2") (pintype "passive"))
      (node (ref "R28") (pin "1") (pinfunction "1_1") (pintype "passive"))
      (node (ref "U4") (pin "12") (pinfunction "X3_12") (pintype "passive"))
    )
    (net (code "42") (name "Net-(U4-X4)") (class "Default")
      (node (ref "D29") (pin "2") (pinfunction "2_2") (pintype "passive"))
      (node (ref "R29") (pin "1") (pinfunction "1_1") (pintype "passive"))
      (node (ref "U4") (pin "1") (pinfunction "X4_1") (pintype "passive"))
    )
    (net (code "43") (name "Net-(U4-X5)") (class "Default")
      (node (ref "D30") (pin "2") (pinfunction "2_2") (pintype "passive"))
      (node (ref "R30") (pin "1") (pinfunction "1_1") (pintype "passive"))
      (node (ref "U4") (pin "5") (pinfunction "X5_5") (pintype "passive"))
    )
    (net (code "44") (name "Net-(U4-X6)") (class "Default")
      (node (ref "D31") (pin "2") (pinfunction "2_2") (pintype "passive"))
      (node (ref "R31") (pin "1") (pinfunction "1_1") (pintype "passive"))
      (node (ref "U4") (pin "2") (pinfunction "X6_2") (pintype "passive"))
    )
    (net (code "45") (name "Net-(U4-X7)") (class "Default")
      (node (ref "D32") (pin "2") (pinfunction "2_2") (pintype "passive"))
      (node (ref "R32") (pin "1") (pinfunction "1_1") (pintype "passive"))
      (node (ref "U4") (pin "4") (pinfunction "X7_4") (pintype "passive"))
    )
    (net (code "46") (name "Net-(U5-X0)") (class "Default")
      (node (ref "D33") (pin "2") (pinfunction "2_2") (pintype "passive"))
      (node (ref "R33") (pin "1") (pinfunction "1_1") (pintype "passive"))
      (node (ref "U5") (pin "13") (pinfunction "X0_13") (pintype "passive"))
    )
    (net (code "47") (name "Net-(U5-X1)") (class "Default")
      (node (ref "D34") (pin "2") (pinfunction "2_2") (pintype "passive"))
      (node (ref "R34") (pin "1") (pinfunction "1_1") (pintype "passive"))
      (node (ref "U5") (pin "14") (pinfunction "X1_14") (pintype "passive"))
    )
    (net (code "48") (name "Net-(U5-X2)") (class "Default")
      (node (ref "D35") (pin "2") (pinfunction "2_2") (pintype "passive"))
      (node (ref "R35") (pin "1") (pinfunction "1_1") (pintype "passive"))
      (node (ref "U5") (pin "15") (pinfunction "X2_15") (pintype "passive"))
    )
    (net (code "49") (name "Net-(U5-X3)") (class "Default")
      (node (ref "D36") (pin "2") (pinfunction "2_2") (pintype "passive"))
      (node (ref "R36") (pin "1") (pinfunction "1_1") (pintype "passive"))
      (node (ref "U5") (pin "12") (pinfunction "X3_12") (pintype "passive"))
    )
    (net (code "50") (name "Net-(U5-X4)") (class "Default")
      (node (ref "D37") (pin "2") (pinfunction "2_2") (pintype "passive"))
      (node (ref "R37") (pin "1") (pinfunction "1_1") (pintype "passive"))
      (node (ref "U5") (pin "1") (pinfunction "X4_1") (pintype "passive"))
    )
    (net (code "51") (name "Net-(U5-X5)") (class "Default")
      (node (ref "D38") (pin "2") (pinfunction "2_2") (pintype "passive"))
      (node (ref "R38") (pin "1") (pinfunction "1_1") (pintype "passive"))
      (node (ref "U5") (pin "5") (pinfunction "X5_5") (pintype "passive"))
    )
    (net (code "52") (name "Net-(U5-X6)") (class "Default")
      (node (ref "D39") (pin "2") (pinfunction "2_2") (pintype "passive"))
      (node (ref "R39") (pin "1") (pinfunction "1_1") (pintype "passive"))
      (node (ref "U5") (pin "2") (pinfunction "X6_2") (pintype "passive"))
    )
    (net (code "53") (name "Net-(U5-X7)") (class "Default")
      (node (ref "D40") (pin "2") (pinfunction "2_2") (pintype "passive"))
      (node (ref "R40") (pin "1") (pinfunction "1_1") (pintype "passive"))
      (node (ref "U5") (pin "4") (pinfunction "X7_4") (pintype "passive"))
    )
    (net (code "54") (name "Net-(U6-X0)") (class "Default")
      (node (ref "D41") (pin "2") (pinfunction "2_2") (pintype "passive"))
      (node (ref "R41") (pin "1") (pinfunction "1_1") (pintype "passive"))
      (node (ref "U6") (pin "13") (pinfunction "X0_13") (pintype "passive"))
    )
    (net (code "55") (name "Net-(U6-X1)") (class "Default")
      (node (ref "D42") (pin "2") (pinfunction "2_2") (pintype "passive"))
      (node (ref "R42") (pin "1") (pinfunction "1_1") (pintype "passive"))
      (node (ref "U6") (pin "14") (pinfunction "X1_14") (pintype "passive"))
    )
    (net (code "56") (name "Net-(U6-X2)") (class "Default")
      (node (ref "D43") (pin "2") (pinfunction "2_2") (pintype "passive"))
      (node (ref "R43") (pin "1") (pinfunction "1_1") (pintype "passive"))
      (node (ref "U6") (pin "15") (pinfunction "X2_15") (pintype "passive"))
    )
    (net (code "57") (name "Net-(U6-X3)") (class "Default")
      (node (ref "D44") (pin "2") (pinfunction "2_2") (pintype "passive"))
      (node (ref "R44") (pin "1") (pinfunction "1_1") (pintype "passive"))
      (node (ref "U6") (pin "12") (pinfunction "X3_12") (pintype "passive"))
    )
    (net (code "58") (name "Net-(U6-X4)") (class "Default")
      (node (ref "D45") (pin "2") (pinfunction "2_2") (pintype "passive"))
      (node (ref "R45") (pin "1") (pinfunction "1_1") (pintype "passive"))
      (node (ref "U6") (pin "1") (pinfunction "X4_1") (pintype "passive"))
    )
    (net (code "59") (name "Net-(U6-X5)") (class "Default")
      (node (ref "D46") (pin "2") (pinfunction "2_2") (pintype "passive"))
      (node (ref "R46") (pin "1") (pinfunction "1_1") (pintype "passive"))
      (node (ref "U6") (pin "5") (pinfunction "X5_5") (pintype "passive"))
    )
    (net (code "60") (name "Net-(U6-X6)") (class "Default")
      (node (ref "D47") (pin "2") (pinfunction "2_2") (pintype "passive"))
      (node (ref "R47") (pin "1") (pinfunction "1_1") (pintype "passive"))
      (node (ref "U6") (pin "2") (pinfunction "X6_2") (pintype "passive"))
    )
    (net (code "61") (name "Net-(U6-X7)") (class "Default")
      (node (ref "D48") (pin "2") (pinfunction "2_2") (pintype "passive"))
      (node (ref "R48") (pin "1") (pinfunction "1_1") (pintype "passive"))
      (node (ref "U6") (pin "4") (pinfunction "X7_4") (pintype "passive"))
    )
    (net (code "62") (name "Net-(U7-X0)") (class "Default")
      (node (ref "D49") (pin "2") (pinfunction "2_2") (pintype "passive"))
      (node (ref "R49") (pin "1") (pinfunction "1_1") (pintype "passive"))
      (node (ref "U7") (pin "13") (pinfunction "X0_13") (pintype "passive"))
    )
    (net (code "63") (name "Net-(U7-X1)") (class "Default")
      (node (ref "D50") (pin "2") (pinfunction "2_2") (pintype "passive"))
      (node (ref "R50") (pin "1") (pinfunction "1_1") (pintype "passive"))
      (node (ref "U7") (pin "14") (pinfunction "X1_14") (pintype "passive"))
    )
    (net (code "64") (name "Net-(U7-X2)") (class "Default")
      (node (ref "D51") (pin "2") (pinfunction "2_2") (pintype "passive"))
      (node (ref "R51") (pin "1") (pinfunction "1_1") (pintype "passive"))
      (node (ref "U7") (pin "15") (pinfunction "X2_15") (pintype "passive"))
    )
    (net (code "65") (name "Net-(U7-X3)") (class "Default")
      (node (ref "D52") (pin "2") (pinfunction "2_2") (pintype "passive"))
      (node (ref "R52") (pin "1") (pinfunction "1_1") (pintype "passive"))
      (node (ref "U7") (pin "12") (pinfunction "X3_12") (pintype "passive"))
    )
    (net (code "66") (name "Net-(U7-X4)") (class "Default")
      (node (ref "D53") (pin "2") (pinfunction "2_2") (pintype "passive"))
      (node (ref "R53") (pin "1") (pinfunction "1_1") (pintype "passive"))
      (node (ref "U7") (pin "1") (pinfunction "X4_1") (pintype "passive"))
    )
    (net (code "67") (name "Net-(U7-X5)") (class "Default")
      (node (ref "D54") (pin "2") (pinfunction "2_2") (pintype "passive"))
      (node (ref "R54") (pin "1") (pinfunction "1_1") (pintype "passive"))
      (node (ref "U7") (pin "5") (pinfunction "X5_5") (pintype "passive"))
    )
    (net (code "68") (name "Net-(U7-X6)") (class "Default")
      (node (ref "D55") (pin "2") (pinfunction "2_2") (pintype "passive"))
      (node (ref "R55") (pin "1") (pinfunction "1_1") (pintype "passive"))
      (node (ref "U7") (pin "2") (pinfunction "X6_2") (pintype "passive"))
    )
    (net (code "69") (name "Net-(U7-X7)") (class "Default")
      (node (ref "D56") (pin "2") (pinfunction "2_2") (pintype "passive"))
      (node (ref "R56") (pin "1") (pinfunction "1_1") (pintype "passive"))
      (node (ref "U7") (pin "4") (pinfunction "X7_4") (pintype "passive"))
    )
    (net (code "70") (name "Net-(U8-X0)") (class "Default")
      (node (ref "D57") (pin "2") (pinfunction "2_2") (pintype "passive"))
      (node (ref "R57") (pin "1") (pinfunction "1_1") (pintype "passive"))
      (node (ref "U8") (pin "13") (pinfunction "X0_13") (pintype "passive"))
    )
    (net (code "71") (name "Net-(U8-X1)") (class "Default")
      (node (ref "D58") (pin "2") (pinfunction "2_2") (pintype "passive"))
      (node (ref "R58") (pin "1") (pinfunction "1_1") (pintype "passive"))
      (node (ref "U8") (pin "14") (pinfunction "X1_14") (pintype "passive"))
    )
    (net (code "72") (name "Net-(U8-X2)") (class "Default")
      (node (ref "D59") (pin "2") (pinfunction "2_2") (pintype "passive"))
      (node (ref "R59") (pin "1") (pinfunction "1_1") (pintype "passive"))
      (node (ref "U8") (pin "15") (pinfunction "X2_15") (pintype "passive"))
    )
    (net (code "73") (name "Net-(U8-X3)") (class "Default")
      (node (ref "D60") (pin "2") (pinfunction "2_2") (pintype "passive"))
      (node (ref "R60") (pin "1") (pinfunction "1_1") (pintype "passive"))
      (node (ref "U8") (pin "12") (pinfunction "X3_12") (pintype "passive"))
    )
    (net (code "74") (name "Net-(U8-X4)") (class "Default")
      (node (ref "D61") (pin "2") (pinfunction "2_2") (pintype "passive"))
      (node (ref "R61") (pin "1") (pinfunction "1_1") (pintype "passive"))
      (node (ref "U8") (pin "1") (pinfunction "X4_1") (pintype "passive"))
    )
    (net (code "75") (name "Net-(U8-X5)") (class "Default")
      (node (ref "D62") (pin "2") (pinfunction "2_2") (pintype "passive"))
      (node (ref "R62") (pin "1") (pinfunction "1_1") (pintype "passive"))
      (node (ref "U8") (pin "5") (pinfunction "X5_5") (pintype "passive"))
    )
    (net (code "76") (name "Net-(U8-X6)") (class "Default")
      (node (ref "D63") (pin "2") (pinfunction "2_2") (pintype "passive"))
      (node (ref "R63") (pin "1") (pinfunction "1_1") (pintype "passive"))
      (node (ref "U8") (pin "2") (pinfunction "X6_2") (pintype "passive"))
    )
    (net (code "77") (name "Net-(U8-X7)") (class "Default")
      (node (ref "D64") (pin "2") (pinfunction "2_2") (pintype "passive"))
      (node (ref "R64") (pin "1") (pinfunction "1_1") (pintype "passive"))
      (node (ref "U8") (pin "4") (pinfunction "X7_4") (pintype "passive"))
    )
    (net (code "78") (name "unconnected-(J1-Pad1)") (class "Default")
      (node (ref "J1") (pin "1") (pinfunction "1_1") (pintype "passive"))
    )
  )
)
